# ConverterBoard.net
KiCad netlist of a schematic drawn in EAGLE
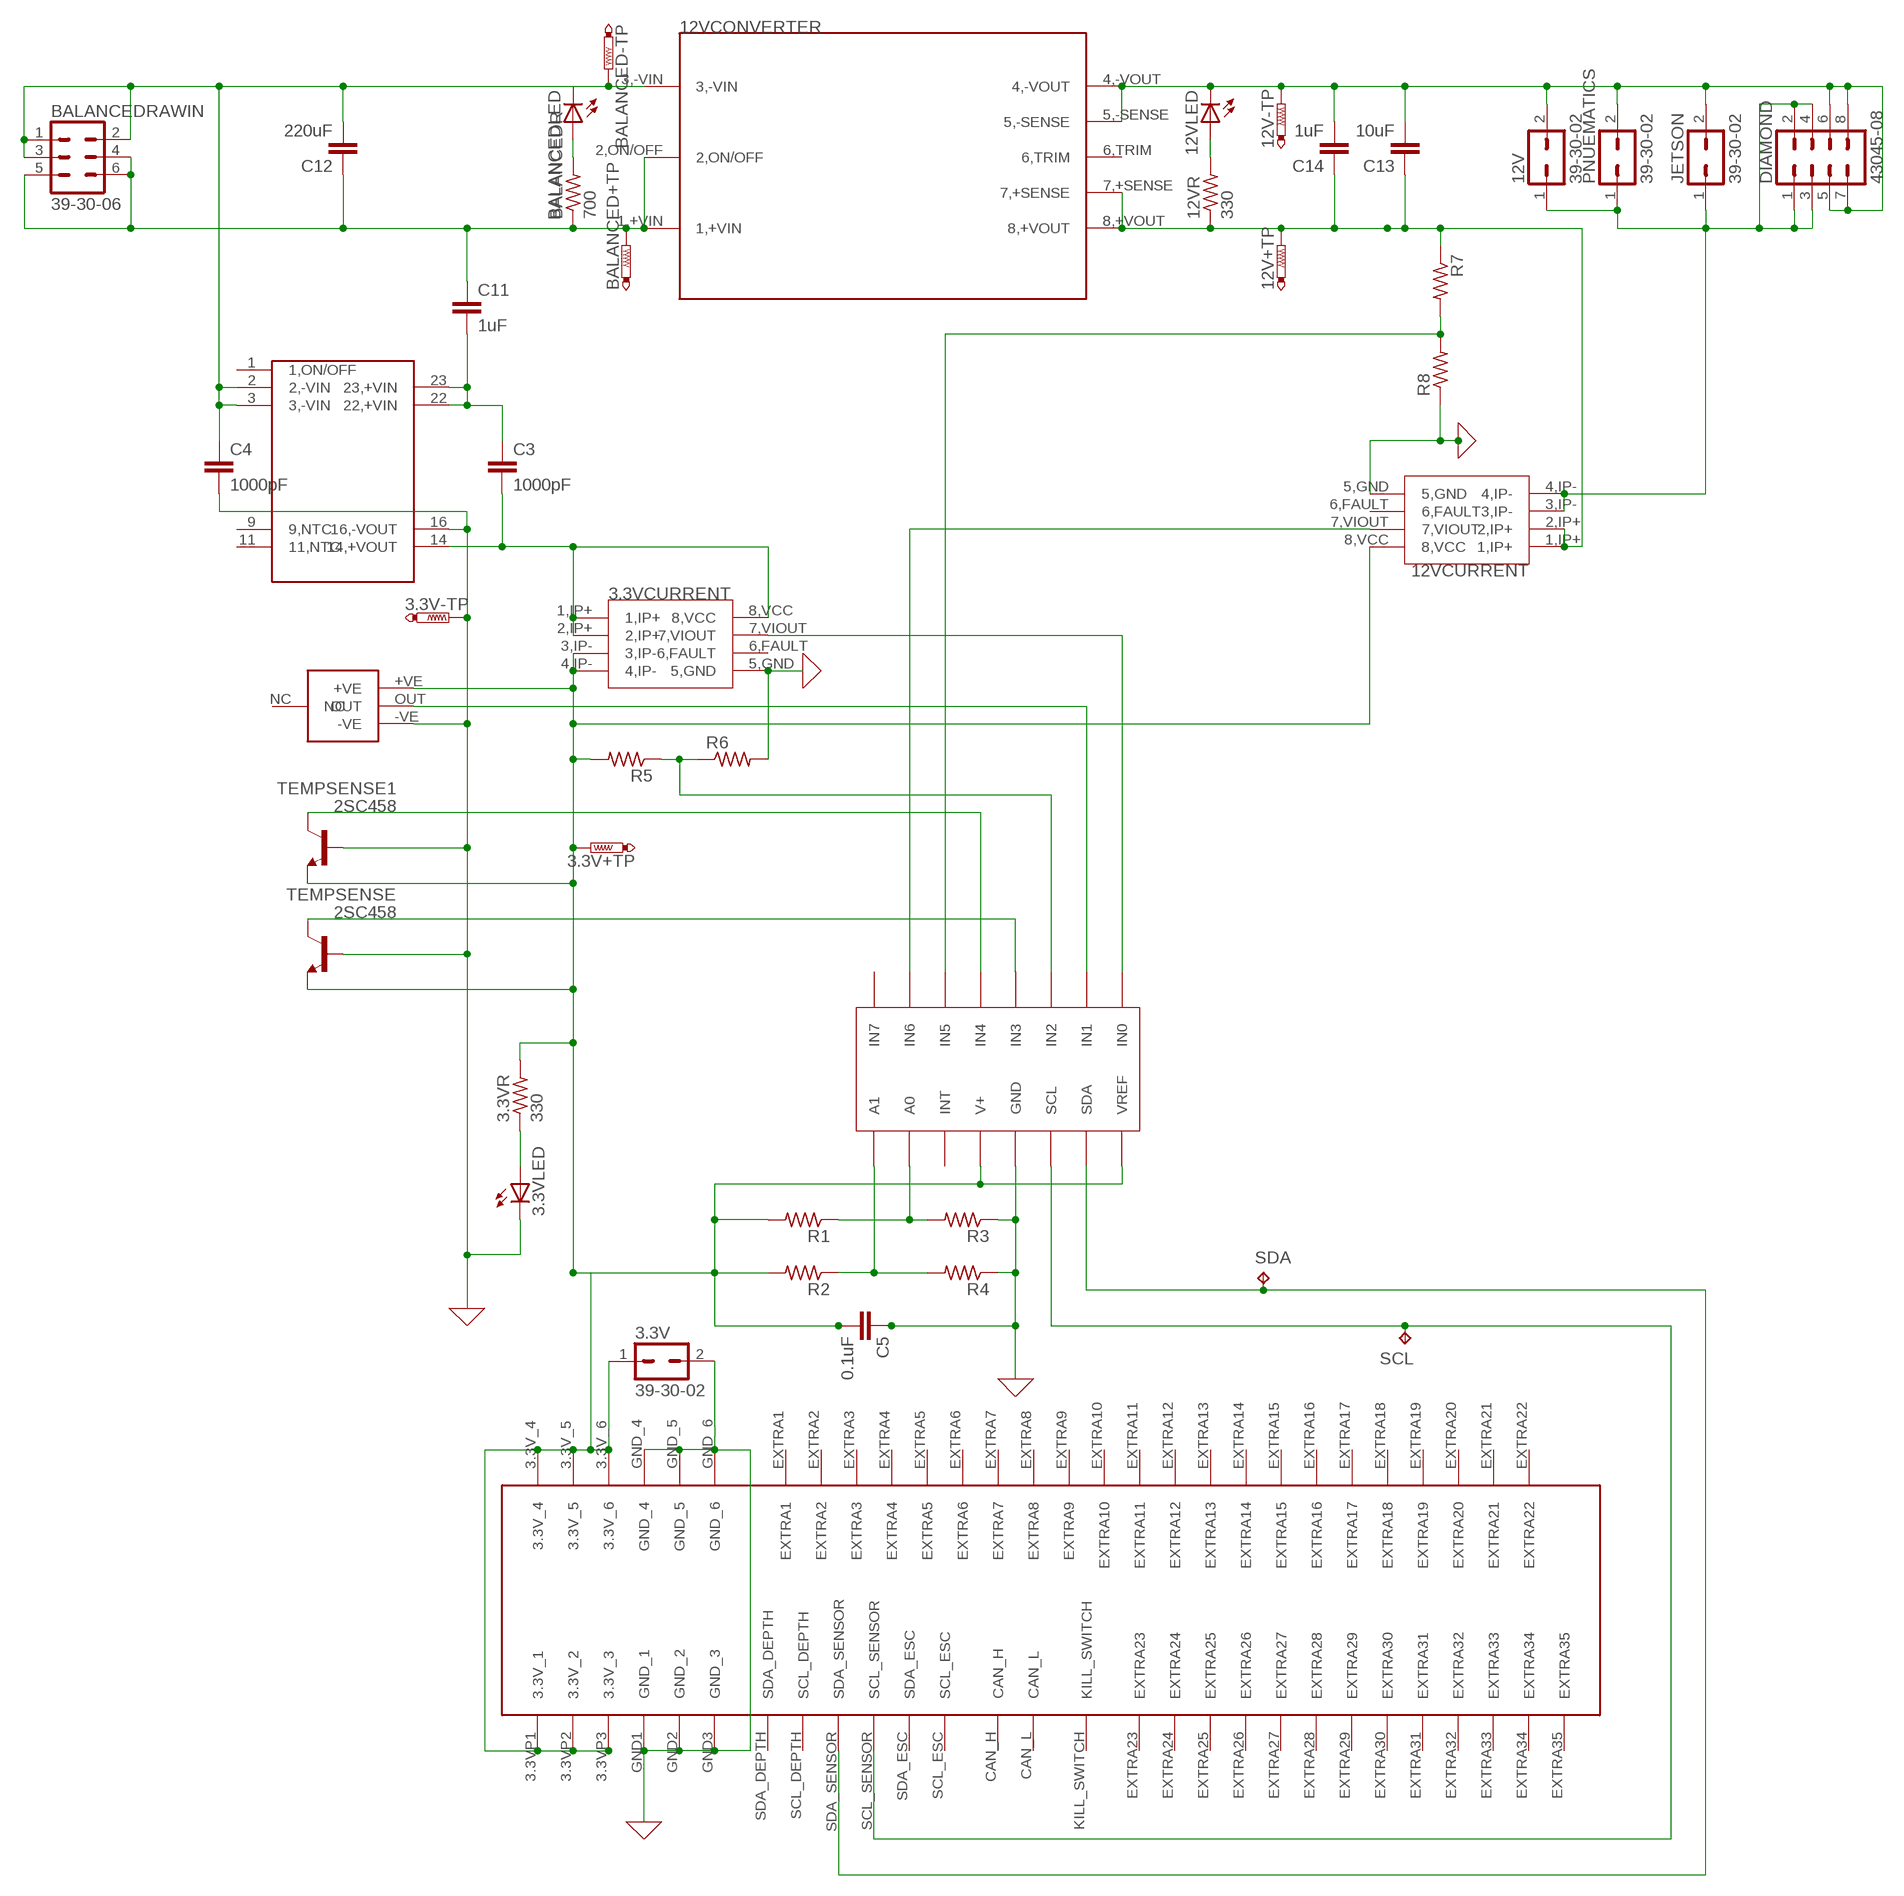
[diagram p0: schematic, sheet 1]

(export (version "E")
  (design (tool "Eeschema 10.0.6"))
  (components
    (comp (ref "3.3V")
      (value "39-30-02")
      (footprint "eagle-import:39-30-_02_")
      (libsource (lib "eagle-import") (part "39-30-?02?"))
    )
    (comp (ref "3.3V+TP")
      (value "PTR1B1,27")
      (footprint "eagle-import:B1,27")
      (libsource (lib "eagle-import") (part "PTR1B1,27"))
    )
    (comp (ref "3.3V-TP")
      (value "PTR1B1,27")
      (footprint "eagle-import:B1,27")
      (libsource (lib "eagle-import") (part "PTR1B1,27"))
    )
    (comp (ref "3.3VCURRENT")
      (value "CURRENTSENS")
      (footprint "eagle-import:CURRENTSENS")
      (libsource (lib "eagle-import") (part "CURRENTSENS"))
    )
    (comp (ref "3.3VLED")
      (value "LTST-S270GKT")
      (footprint "eagle-import:LTST-S270GKT")
      (libsource (lib "eagle-import") (part "LTST-S270GKT"))
    )
    (comp (ref "3.3VR")
      (value "330")
      (footprint "eagle-import:0204_7")
      (libsource (lib "eagle-import") (part "R-US_0204/7"))
    )
    (comp (ref "12V")
      (value "39-30-02")
      (footprint "eagle-import:39-30-_02_")
      (libsource (lib "eagle-import") (part "39-30-?02?"))
    )
    (comp (ref "12V+TP")
      (value "PTR1B1,27")
      (footprint "eagle-import:B1,27")
      (libsource (lib "eagle-import") (part "PTR1B1,27"))
    )
    (comp (ref "12V-TP")
      (value "PTR1B1,27")
      (footprint "eagle-import:B1,27")
      (libsource (lib "eagle-import") (part "PTR1B1,27"))
    )
    (comp (ref "12VCONVERTER")
      (value "12VCONV")
      (footprint "eagle-import:12VCONV")
      (libsource (lib "eagle-import") (part "12VCONV"))
    )
    (comp (ref "12VCURRENT")
      (value "CURRENTSENS")
      (footprint "eagle-import:CURRENTSENS")
      (libsource (lib "eagle-import") (part "CURRENTSENS"))
    )
    (comp (ref "12VLED")
      (value "LTST-S270GKT")
      (footprint "eagle-import:LTST-S270GKT")
      (libsource (lib "eagle-import") (part "LTST-S270GKT"))
    )
    (comp (ref "12VR")
      (value "330")
      (footprint "eagle-import:0204_7")
      (libsource (lib "eagle-import") (part "R-US_0204/7"))
    )
    (comp (ref "ADC")
      (value "ADC128D818")
      (footprint "eagle-import:TSSOP-16")
      (libsource (lib "eagle-import") (part "ADC128D818"))
    )
    (comp (ref "BALANCED+TP")
      (value "PTR1B1,27")
      (footprint "eagle-import:B1,27")
      (libsource (lib "eagle-import") (part "PTR1B1,27"))
    )
    (comp (ref "BALANCED-TP")
      (value "PTR1B1,27")
      (footprint "eagle-import:B1,27")
      (libsource (lib "eagle-import") (part "PTR1B1,27"))
    )
    (comp (ref "BALANCEDLED")
      (value "LTST-S270GKT")
      (footprint "eagle-import:LTST-S270GKT")
      (libsource (lib "eagle-import") (part "LTST-S270GKT"))
    )
    (comp (ref "BALANCEDR")
      (value "700")
      (footprint "eagle-import:0204_7")
      (libsource (lib "eagle-import") (part "R-US_0204/7"))
    )
    (comp (ref "BALANCEDRAWIN")
      (value "39-30-06")
      (footprint "eagle-import:39-30-_06_")
      (libsource (lib "eagle-import") (part "39-30-?06?"))
    )
    (comp (ref "C3")
      (value "1000pF")
      (footprint "eagle-import:C5B3")
      (libsource (lib "eagle-import") (part "C5/3"))
    )
    (comp (ref "C4")
      (value "1000pF")
      (footprint "eagle-import:C5B3")
      (libsource (lib "eagle-import") (part "C5/3"))
    )
    (comp (ref "C5")
      (value "0.1uF")
      (footprint "eagle-import:C2.5-2")
      (libsource (lib "eagle-import") (part "C2.5/2"))
    )
    (comp (ref "C11")
      (value "1uF")
      (footprint "eagle-import:C5B3")
      (libsource (lib "eagle-import") (part "C5/3"))
    )
    (comp (ref "C12")
      (value "220uF")
      (footprint "eagle-import:C5B3")
      (libsource (lib "eagle-import") (part "C5/3"))
    )
    (comp (ref "C13")
      (value "10uF")
      (footprint "eagle-import:C5B3")
      (libsource (lib "eagle-import") (part "C5/3"))
    )
    (comp (ref "C14")
      (value "1uF")
      (footprint "eagle-import:C5B3")
      (libsource (lib "eagle-import") (part "C5/3"))
    )
    (comp (ref "DIAMOND")
      (value "43045-08")
      (footprint "eagle-import:43045-08")
      (libsource (lib "eagle-import") (part "43045-08"))
    )
    (comp (ref "JETSON")
      (value "39-30-02")
      (footprint "eagle-import:39-30-_02_")
      (libsource (lib "eagle-import") (part "39-30-?02?"))
    )
    (comp (ref "PNUEMATICS")
      (value "39-30-02")
      (footprint "eagle-import:39-30-_02_")
      (libsource (lib "eagle-import") (part "39-30-?02?"))
    )
    (comp (ref "R1")
      (value "R-US_0204/7")
      (footprint "eagle-import:0204_7")
      (libsource (lib "eagle-import") (part "R-US_0204/7"))
    )
    (comp (ref "R2")
      (value "R-US_0204/7")
      (footprint "eagle-import:0204_7")
      (libsource (lib "eagle-import") (part "R-US_0204/7"))
    )
    (comp (ref "R3")
      (value "R-US_0204/7")
      (footprint "eagle-import:0204_7")
      (libsource (lib "eagle-import") (part "R-US_0204/7"))
    )
    (comp (ref "R4")
      (value "R-US_0204/7")
      (footprint "eagle-import:0204_7")
      (libsource (lib "eagle-import") (part "R-US_0204/7"))
    )
    (comp (ref "R5")
      (value "R-US_0204/7")
      (footprint "eagle-import:0204_7")
      (libsource (lib "eagle-import") (part "R-US_0204/7"))
    )
    (comp (ref "R6")
      (value "R-US_0204/7")
      (footprint "eagle-import:0204_7")
      (libsource (lib "eagle-import") (part "R-US_0204/7"))
    )
    (comp (ref "R7")
      (value "R-US_0204/7")
      (footprint "eagle-import:0204_7")
      (libsource (lib "eagle-import") (part "R-US_0204/7"))
    )
    (comp (ref "R8")
      (value "R-US_0204/7")
      (footprint "eagle-import:0204_7")
      (libsource (lib "eagle-import") (part "R-US_0204/7"))
    )
    (comp (ref "SCL")
      (value "TPPAD1-20")
      (footprint "eagle-import:P1-20")
      (libsource (lib "eagle-import") (part "TPPAD1-20"))
    )
    (comp (ref "SDA")
      (value "TPPAD1-20")
      (footprint "eagle-import:P1-20")
      (libsource (lib "eagle-import") (part "TPPAD1-20"))
    )
    (comp (ref "TEMPSENSE")
      (value "2SC458")
      (footprint "eagle-import:TO92-ECB")
      (libsource (lib "eagle-import") (part "2SC458"))
    )
    (comp (ref "TEMPSENSE1")
      (value "2SC458")
      (footprint "eagle-import:TO92-ECB")
      (libsource (lib "eagle-import") (part "2SC458"))
    )
    (comp (ref "U$2")
      (value "3.3VCONV")
      (footprint "eagle-import:3.3VCONV")
      (libsource (lib "eagle-import") (part "3.3VCONV"))
    )
    (comp (ref "U$3")
      (value "5530843")
      (footprint "eagle-import:5530843-6-BOARDFINGERS")
      (libsource (lib "eagle-import") (part "5530843"))
    )
    (comp (ref "U$6")
      (value "HUMIDITYSENSOR")
      (footprint "eagle-import:HUMIDITYSENSOR")
      (libsource (lib "eagle-import") (part "HUMIDITYSENSOR"))
    )
  )
  (nets
    (net (code "1") (name "GND") (class "Default")
      (node (ref "12V") (pin "2") (pinfunction "2_2") (pintype "passive"))
      (node (ref "12V-TP") (pin "TP") (pinfunction "TP_TP") (pintype "input"))
      (node (ref "12VCONVERTER") (pin "4,-VOUT") (pinfunction "4,-VOUT_4,-VOUT") (pintype "bidirectional"))
      (node (ref "12VCONVERTER") (pin "5,-SENSE") (pinfunction "5,-SENSE_5,-SENSE") (pintype "bidirectional"))
      (node (ref "12VCURRENT") (pin "5,GND") (pinfunction "5,GND_5,GND") (pintype "bidirectional"))
      (node (ref "12VLED") (pin "CATHODE") (pinfunction "C_CATHODE") (pintype "passive"))
      (node (ref "3.3V") (pin "2") (pinfunction "2_2") (pintype "passive"))
      (node (ref "3.3V-TP") (pin "TP") (pinfunction "TP_TP") (pintype "input"))
      (node (ref "3.3VCURRENT") (pin "5,GND") (pinfunction "5,GND_5,GND") (pintype "bidirectional"))
      (node (ref "3.3VLED") (pin "CATHODE") (pinfunction "C_CATHODE") (pintype "passive"))
      (node (ref "ADC") (pin "GND") (pinfunction "GND_GND") (pintype "bidirectional"))
      (node (ref "C13") (pin "2") (pinfunction "2_2") (pintype "passive"))
      (node (ref "C14") (pin "2") (pinfunction "2_2") (pintype "passive"))
      (node (ref "C4") (pin "2") (pinfunction "2_2") (pintype "passive"))
      (node (ref "C5") (pin "1") (pinfunction "1_1") (pintype "passive"))
      (node (ref "DIAMOND") (pin "5") (pinfunction "5_5") (pintype "passive"))
      (node (ref "DIAMOND") (pin "6") (pinfunction "6_6") (pintype "passive"))
      (node (ref "DIAMOND") (pin "7") (pinfunction "7_7") (pintype "passive"))
      (node (ref "DIAMOND") (pin "8") (pinfunction "8_8") (pintype "passive"))
      (node (ref "JETSON") (pin "2") (pinfunction "2_2") (pintype "passive"))
      (node (ref "PNUEMATICS") (pin "2") (pinfunction "2_2") (pintype "passive"))
      (node (ref "R3") (pin "1") (pinfunction "1_1") (pintype "passive"))
      (node (ref "R4") (pin "1") (pinfunction "1_1") (pintype "passive"))
      (node (ref "R6") (pin "2") (pinfunction "2_2") (pintype "passive"))
      (node (ref "R8") (pin "1") (pinfunction "1_1") (pintype "passive"))
      (node (ref "TEMPSENSE") (pin "B") (pinfunction "B_B") (pintype "passive"))
      (node (ref "TEMPSENSE1") (pin "B") (pinfunction "B_B") (pintype "passive"))
      (node (ref "U$2") (pin "16") (pinfunction "16,-VOUT_16") (pintype "bidirectional"))
      (node (ref "U$3") (pin "GND1") (pinfunction "GND_1_GND1") (pintype "bidirectional"))
      (node (ref "U$3") (pin "GND2") (pinfunction "GND_2_GND2") (pintype "bidirectional"))
      (node (ref "U$3") (pin "GND3") (pinfunction "GND_3_GND3") (pintype "bidirectional"))
      (node (ref "U$3") (pin "GND_4") (pinfunction "GND_4_GND_4") (pintype "bidirectional"))
      (node (ref "U$3") (pin "GND_5") (pinfunction "GND_5_GND_5") (pintype "bidirectional"))
      (node (ref "U$3") (pin "GND_6") (pinfunction "GND_6_GND_6") (pintype "bidirectional"))
      (node (ref "U$6") (pin "-VE") (pinfunction "-VE_-VE") (pintype "bidirectional"))
    )
    (net (code "2") (name "Net-(3.3VCURRENT-Pad7,VIOUT)") (class "Default")
      (node (ref "3.3VCURRENT") (pin "7,VIOUT") (pinfunction "7,VIOUT_7,VIOUT") (pintype "bidirectional"))
      (node (ref "ADC") (pin "IN0") (pinfunction "IN0_IN0") (pintype "bidirectional"))
    )
    (net (code "3") (name "Net-(3.3VLED-A)") (class "Default")
      (node (ref "3.3VLED") (pin "ANODE") (pinfunction "A_ANODE") (pintype "passive"))
      (node (ref "3.3VR") (pin "1") (pinfunction "1_1") (pintype "passive"))
    )
    (net (code "4") (name "Net-(12V+TP-PadTP)") (class "Default")
      (node (ref "12V+TP") (pin "TP") (pinfunction "TP_TP") (pintype "input"))
      (node (ref "12VCONVERTER") (pin "7,+SENSE") (pinfunction "7,+SENSE_7,+SENSE") (pintype "bidirectional"))
      (node (ref "12VCONVERTER") (pin "8,+VOUT") (pinfunction "8,+VOUT_8,+VOUT") (pintype "bidirectional"))
      (node (ref "12VCURRENT") (pin "1,IP+") (pinfunction "1,IP+_1,IP+") (pintype "bidirectional"))
      (node (ref "12VCURRENT") (pin "2,IP+") (pinfunction "2,IP+_2,IP+") (pintype "bidirectional"))
      (node (ref "12VR") (pin "1") (pinfunction "1_1") (pintype "passive"))
      (node (ref "C13") (pin "1") (pinfunction "1_1") (pintype "passive"))
      (node (ref "C14") (pin "1") (pinfunction "1_1") (pintype "passive"))
      (node (ref "R7") (pin "1") (pinfunction "1_1") (pintype "passive"))
    )
    (net (code "5") (name "Net-(12V-Pad1)") (class "Default")
      (node (ref "12V") (pin "1") (pinfunction "1_1") (pintype "passive"))
      (node (ref "12VCURRENT") (pin "3,IP-") (pinfunction "3,IP-_3,IP-") (pintype "bidirectional"))
      (node (ref "12VCURRENT") (pin "4,IP-") (pinfunction "4,IP-_4,IP-") (pintype "bidirectional"))
      (node (ref "DIAMOND") (pin "1") (pinfunction "1_1") (pintype "passive"))
      (node (ref "DIAMOND") (pin "2") (pinfunction "2_2") (pintype "passive"))
      (node (ref "DIAMOND") (pin "3") (pinfunction "3_3") (pintype "passive"))
      (node (ref "DIAMOND") (pin "4") (pinfunction "4_4") (pintype "passive"))
      (node (ref "JETSON") (pin "1") (pinfunction "1_1") (pintype "passive"))
      (node (ref "PNUEMATICS") (pin "1") (pinfunction "1_1") (pintype "passive"))
    )
    (net (code "6") (name "Net-(12VCONVERTER-Pad1,+VIN)") (class "Default")
      (node (ref "12VCONVERTER") (pin "1,+VIN") (pinfunction "1,+VIN_1,+VIN") (pintype "bidirectional"))
      (node (ref "12VCONVERTER") (pin "2,ON/OFF") (pinfunction "2,ON/OFF_2,ON/OFF") (pintype "bidirectional"))
      (node (ref "BALANCED+TP") (pin "TP") (pinfunction "TP_TP") (pintype "input"))
      (node (ref "BALANCEDR") (pin "1") (pinfunction "1_1") (pintype "passive"))
      (node (ref "BALANCEDRAWIN") (pin "4") (pinfunction "4_4") (pintype "passive"))
      (node (ref "BALANCEDRAWIN") (pin "5") (pinfunction "5_5") (pintype "passive"))
      (node (ref "BALANCEDRAWIN") (pin "6") (pinfunction "6_6") (pintype "passive"))
      (node (ref "C11") (pin "1") (pinfunction "1_1") (pintype "passive"))
      (node (ref "C12") (pin "1") (pinfunction "1_1") (pintype "passive"))
    )
    (net (code "7") (name "Net-(12VCURRENT-Pad7,VIOUT)") (class "Default")
      (node (ref "12VCURRENT") (pin "7,VIOUT") (pinfunction "7,VIOUT_7,VIOUT") (pintype "bidirectional"))
      (node (ref "ADC") (pin "IN6") (pinfunction "IN6_IN6") (pintype "bidirectional"))
    )
    (net (code "8") (name "Net-(12VLED-A)") (class "Default")
      (node (ref "12VLED") (pin "ANODE") (pinfunction "A_ANODE") (pintype "passive"))
      (node (ref "12VR") (pin "2") (pinfunction "2_2") (pintype "passive"))
    )
    (net (code "9") (name "Net-(ADC-PadA0)") (class "Default")
      (node (ref "ADC") (pin "A0") (pinfunction "A0_A0") (pintype "bidirectional"))
      (node (ref "R1") (pin "1") (pinfunction "1_1") (pintype "passive"))
      (node (ref "R3") (pin "2") (pinfunction "2_2") (pintype "passive"))
    )
    (net (code "10") (name "Net-(ADC-PadA1)") (class "Default")
      (node (ref "ADC") (pin "A1") (pinfunction "A1_A1") (pintype "bidirectional"))
      (node (ref "R2") (pin "1") (pinfunction "1_1") (pintype "passive"))
      (node (ref "R4") (pin "2") (pinfunction "2_2") (pintype "passive"))
    )
    (net (code "11") (name "Net-(ADC-PadIN1)") (class "Default")
      (node (ref "ADC") (pin "IN1") (pinfunction "IN1_IN1") (pintype "bidirectional"))
      (node (ref "U$6") (pin "OUT") (pinfunction "OUT_OUT") (pintype "bidirectional"))
    )
    (net (code "12") (name "Net-(ADC-PadIN2)") (class "Default")
      (node (ref "ADC") (pin "IN2") (pinfunction "IN2_IN2") (pintype "bidirectional"))
      (node (ref "R5") (pin "1") (pinfunction "1_1") (pintype "passive"))
      (node (ref "R6") (pin "1") (pinfunction "1_1") (pintype "passive"))
    )
    (net (code "13") (name "Net-(ADC-PadIN3)") (class "Default")
      (node (ref "ADC") (pin "IN3") (pinfunction "IN3_IN3") (pintype "bidirectional"))
      (node (ref "TEMPSENSE") (pin "C") (pinfunction "C_C") (pintype "passive"))
    )
    (net (code "14") (name "Net-(ADC-PadIN4)") (class "Default")
      (node (ref "ADC") (pin "IN4") (pinfunction "IN4_IN4") (pintype "bidirectional"))
      (node (ref "TEMPSENSE1") (pin "C") (pinfunction "C_C") (pintype "passive"))
    )
    (net (code "15") (name "Net-(ADC-PadIN5)") (class "Default")
      (node (ref "ADC") (pin "IN5") (pinfunction "IN5_IN5") (pintype "bidirectional"))
      (node (ref "R7") (pin "2") (pinfunction "2_2") (pintype "passive"))
      (node (ref "R8") (pin "2") (pinfunction "2_2") (pintype "passive"))
    )
    (net (code "16") (name "Net-(ADC-PadSCL)") (class "Default")
      (node (ref "ADC") (pin "SCL") (pinfunction "SCL_SCL") (pintype "bidirectional"))
      (node (ref "SCL") (pin "TP") (pinfunction "TP_TP") (pintype "input"))
      (node (ref "U$3") (pin "SCL_SENSOR") (pinfunction "SCL_SENSOR_SCL_SENSOR") (pintype "bidirectional"))
    )
    (net (code "17") (name "Net-(ADC-PadSDA)") (class "Default")
      (node (ref "ADC") (pin "SDA") (pinfunction "SDA_SDA") (pintype "bidirectional"))
      (node (ref "SDA") (pin "TP") (pinfunction "TP_TP") (pintype "input"))
      (node (ref "U$3") (pin "SDA_SENSOR") (pinfunction "SDA_SENSOR_SDA_SENSOR") (pintype "bidirectional"))
    )
    (net (code "18") (name "Net-(BALANCEDLED-A)") (class "Default")
      (node (ref "BALANCEDLED") (pin "ANODE") (pinfunction "A_ANODE") (pintype "passive"))
      (node (ref "BALANCEDR") (pin "2") (pinfunction "2_2") (pintype "passive"))
    )
    (net (code "19") (name "Net-(BALANCEDLED-C)") (class "Default")
      (node (ref "12VCONVERTER") (pin "3,-VIN") (pinfunction "3,-VIN_3,-VIN") (pintype "bidirectional"))
      (node (ref "BALANCED-TP") (pin "TP") (pinfunction "TP_TP") (pintype "input"))
      (node (ref "BALANCEDLED") (pin "CATHODE") (pinfunction "C_CATHODE") (pintype "passive"))
      (node (ref "BALANCEDRAWIN") (pin "1") (pinfunction "1_1") (pintype "passive"))
      (node (ref "BALANCEDRAWIN") (pin "2") (pinfunction "2_2") (pintype "passive"))
      (node (ref "BALANCEDRAWIN") (pin "3") (pinfunction "3_3") (pintype "passive"))
      (node (ref "C12") (pin "2") (pinfunction "2_2") (pintype "passive"))
      (node (ref "C4") (pin "1") (pinfunction "1_1") (pintype "passive"))
      (node (ref "U$2") (pin "2") (pinfunction "2,-VIN_2") (pintype "bidirectional"))
      (node (ref "U$2") (pin "3") (pinfunction "3,-VIN_3") (pintype "bidirectional"))
    )
    (net (code "20") (name "Net-(U$2-14,+VOUT)") (class "Default")
      (node (ref "3.3VCURRENT") (pin "1,IP+") (pinfunction "1,IP+_1,IP+") (pintype "bidirectional"))
      (node (ref "3.3VCURRENT") (pin "2,IP+") (pinfunction "2,IP+_2,IP+") (pintype "bidirectional"))
      (node (ref "3.3VCURRENT") (pin "8,VCC") (pinfunction "8,VCC_8,VCC") (pintype "bidirectional"))
      (node (ref "C3") (pin "2") (pinfunction "2_2") (pintype "passive"))
      (node (ref "U$2") (pin "14") (pinfunction "14,+VOUT_14") (pintype "bidirectional"))
    )
    (net (code "21") (name "Net-(U$2-22,+VIN)") (class "Default")
      (node (ref "C11") (pin "2") (pinfunction "2_2") (pintype "passive"))
      (node (ref "C3") (pin "1") (pinfunction "1_1") (pintype "passive"))
      (node (ref "U$2") (pin "22") (pinfunction "22,+VIN_22") (pintype "bidirectional"))
      (node (ref "U$2") (pin "23") (pinfunction "23,+VIN_23") (pintype "bidirectional"))
    )
    (net (code "22") (name "Net-(U$3-3.3V_1)") (class "Default")
      (node (ref "12VCURRENT") (pin "8,VCC") (pinfunction "8,VCC_8,VCC") (pintype "bidirectional"))
      (node (ref "3.3V") (pin "1") (pinfunction "1_1") (pintype "passive"))
      (node (ref "3.3V+TP") (pin "TP") (pinfunction "TP_TP") (pintype "input"))
      (node (ref "3.3VCURRENT") (pin "3,IP-") (pinfunction "3,IP-_3,IP-") (pintype "bidirectional"))
      (node (ref "3.3VCURRENT") (pin "4,IP-") (pinfunction "4,IP-_4,IP-") (pintype "bidirectional"))
      (node (ref "3.3VR") (pin "2") (pinfunction "2_2") (pintype "passive"))
      (node (ref "ADC") (pin "V+") (pinfunction "V+_V+") (pintype "bidirectional"))
      (node (ref "ADC") (pin "VREF") (pinfunction "VREF_VREF") (pintype "bidirectional"))
      (node (ref "C5") (pin "2") (pinfunction "2_2") (pintype "passive"))
      (node (ref "R1") (pin "2") (pinfunction "2_2") (pintype "passive"))
      (node (ref "R2") (pin "2") (pinfunction "2_2") (pintype "passive"))
      (node (ref "R5") (pin "2") (pinfunction "2_2") (pintype "passive"))
      (node (ref "TEMPSENSE") (pin "E") (pinfunction "E_E") (pintype "passive"))
      (node (ref "TEMPSENSE1") (pin "E") (pinfunction "E_E") (pintype "passive"))
      (node (ref "U$3") (pin "3.3VP1") (pinfunction "3.3V_1_3.3VP1") (pintype "bidirectional"))
      (node (ref "U$3") (pin "3.3VP2") (pinfunction "3.3V_2_3.3VP2") (pintype "bidirectional"))
      (node (ref "U$3") (pin "3.3VP3") (pinfunction "3.3V_3_3.3VP3") (pintype "bidirectional"))
      (node (ref "U$3") (pin "3.3V_4") (pinfunction "3.3V_4_3.3V_4") (pintype "bidirectional"))
      (node (ref "U$3") (pin "3.3V_5") (pinfunction "3.3V_5_3.3V_5") (pintype "bidirectional"))
      (node (ref "U$3") (pin "3.3V_6") (pinfunction "3.3V_6_3.3V_6") (pintype "bidirectional"))
      (node (ref "U$6") (pin "+VE") (pinfunction "+VE_+VE") (pintype "bidirectional"))
    )
    (net (code "23") (name "unconnected-(3.3VCURRENT-Pad6,FAULT)") (class "Default")
      (node (ref "3.3VCURRENT") (pin "6,FAULT") (pinfunction "6,FAULT_6,FAULT") (pintype "bidirectional"))
    )
    (net (code "24") (name "unconnected-(12VCONVERTER-Pad6,TRIM)") (class "Default")
      (node (ref "12VCONVERTER") (pin "6,TRIM") (pinfunction "6,TRIM_6,TRIM") (pintype "bidirectional"))
    )
    (net (code "25") (name "unconnected-(12VCURRENT-Pad6,FAULT)") (class "Default")
      (node (ref "12VCURRENT") (pin "6,FAULT") (pinfunction "6,FAULT_6,FAULT") (pintype "bidirectional"))
    )
    (net (code "26") (name "unconnected-(ADC-PadIN7)") (class "Default")
      (node (ref "ADC") (pin "IN7") (pinfunction "IN7_IN7") (pintype "bidirectional"))
    )
    (net (code "27") (name "unconnected-(ADC-PadINT)") (class "Default")
      (node (ref "ADC") (pin "INT") (pinfunction "INT_INT") (pintype "bidirectional"))
    )
    (net (code "28") (name "unconnected-(U$2-1,ON{slash}OFF-Pad1)") (class "Default")
      (node (ref "U$2") (pin "1") (pinfunction "1,ON/OFF_1") (pintype "bidirectional"))
    )
    (net (code "29") (name "unconnected-(U$2-9,NTC-Pad9)") (class "Default")
      (node (ref "U$2") (pin "9") (pinfunction "9,NTC_9") (pintype "bidirectional"))
    )
    (net (code "30") (name "unconnected-(U$2-11,NTC-Pad11)") (class "Default")
      (node (ref "U$2") (pin "11") (pinfunction "11,NTC_11") (pintype "bidirectional"))
    )
    (net (code "31") (name "unconnected-(U$3-PadCAN_H)") (class "Default")
      (node (ref "U$3") (pin "CAN_H") (pinfunction "CAN_H_CAN_H") (pintype "bidirectional"))
    )
    (net (code "32") (name "unconnected-(U$3-PadCAN_L)") (class "Default")
      (node (ref "U$3") (pin "CAN_L") (pinfunction "CAN_L_CAN_L") (pintype "bidirectional"))
    )
    (net (code "33") (name "unconnected-(U$3-PadEXTRA1)") (class "Default")
      (node (ref "U$3") (pin "EXTRA1") (pinfunction "EXTRA1_EXTRA1") (pintype "bidirectional"))
    )
    (net (code "34") (name "unconnected-(U$3-PadEXTRA2)") (class "Default")
      (node (ref "U$3") (pin "EXTRA2") (pinfunction "EXTRA2_EXTRA2") (pintype "bidirectional"))
    )
    (net (code "35") (name "unconnected-(U$3-PadEXTRA3)") (class "Default")
      (node (ref "U$3") (pin "EXTRA3") (pinfunction "EXTRA3_EXTRA3") (pintype "bidirectional"))
    )
    (net (code "36") (name "unconnected-(U$3-PadEXTRA4)") (class "Default")
      (node (ref "U$3") (pin "EXTRA4") (pinfunction "EXTRA4_EXTRA4") (pintype "bidirectional"))
    )
    (net (code "37") (name "unconnected-(U$3-PadEXTRA5)") (class "Default")
      (node (ref "U$3") (pin "EXTRA5") (pinfunction "EXTRA5_EXTRA5") (pintype "bidirectional"))
    )
    (net (code "38") (name "unconnected-(U$3-PadEXTRA6)") (class "Default")
      (node (ref "U$3") (pin "EXTRA6") (pinfunction "EXTRA6_EXTRA6") (pintype "bidirectional"))
    )
    (net (code "39") (name "unconnected-(U$3-PadEXTRA7)") (class "Default")
      (node (ref "U$3") (pin "EXTRA7") (pinfunction "EXTRA7_EXTRA7") (pintype "bidirectional"))
    )
    (net (code "40") (name "unconnected-(U$3-PadEXTRA8)") (class "Default")
      (node (ref "U$3") (pin "EXTRA8") (pinfunction "EXTRA8_EXTRA8") (pintype "bidirectional"))
    )
    (net (code "41") (name "unconnected-(U$3-PadEXTRA9)") (class "Default")
      (node (ref "U$3") (pin "EXTRA9") (pinfunction "EXTRA9_EXTRA9") (pintype "bidirectional"))
    )
    (net (code "42") (name "unconnected-(U$3-PadEXTRA10)") (class "Default")
      (node (ref "U$3") (pin "EXTRA10") (pinfunction "EXTRA10_EXTRA10") (pintype "bidirectional"))
    )
    (net (code "43") (name "unconnected-(U$3-PadEXTRA11)") (class "Default")
      (node (ref "U$3") (pin "EXTRA11") (pinfunction "EXTRA11_EXTRA11") (pintype "bidirectional"))
    )
    (net (code "44") (name "unconnected-(U$3-PadEXTRA12)") (class "Default")
      (node (ref "U$3") (pin "EXTRA12") (pinfunction "EXTRA12_EXTRA12") (pintype "bidirectional"))
    )
    (net (code "45") (name "unconnected-(U$3-PadEXTRA13)") (class "Default")
      (node (ref "U$3") (pin "EXTRA13") (pinfunction "EXTRA13_EXTRA13") (pintype "bidirectional"))
    )
    (net (code "46") (name "unconnected-(U$3-PadEXTRA14)") (class "Default")
      (node (ref "U$3") (pin "EXTRA14") (pinfunction "EXTRA14_EXTRA14") (pintype "bidirectional"))
    )
    (net (code "47") (name "unconnected-(U$3-PadEXTRA15)") (class "Default")
      (node (ref "U$3") (pin "EXTRA15") (pinfunction "EXTRA15_EXTRA15") (pintype "bidirectional"))
    )
    (net (code "48") (name "unconnected-(U$3-PadEXTRA16)") (class "Default")
      (node (ref "U$3") (pin "EXTRA16") (pinfunction "EXTRA16_EXTRA16") (pintype "bidirectional"))
    )
    (net (code "49") (name "unconnected-(U$3-PadEXTRA17)") (class "Default")
      (node (ref "U$3") (pin "EXTRA17") (pinfunction "EXTRA17_EXTRA17") (pintype "bidirectional"))
    )
    (net (code "50") (name "unconnected-(U$3-PadEXTRA18)") (class "Default")
      (node (ref "U$3") (pin "EXTRA18") (pinfunction "EXTRA18_EXTRA18") (pintype "bidirectional"))
    )
    (net (code "51") (name "unconnected-(U$3-PadEXTRA19)") (class "Default")
      (node (ref "U$3") (pin "EXTRA19") (pinfunction "EXTRA19_EXTRA19") (pintype "bidirectional"))
    )
    (net (code "52") (name "unconnected-(U$3-PadEXTRA20)") (class "Default")
      (node (ref "U$3") (pin "EXTRA20") (pinfunction "EXTRA20_EXTRA20") (pintype "bidirectional"))
    )
    (net (code "53") (name "unconnected-(U$3-PadEXTRA21)") (class "Default")
      (node (ref "U$3") (pin "EXTRA21") (pinfunction "EXTRA21_EXTRA21") (pintype "bidirectional"))
    )
    (net (code "54") (name "unconnected-(U$3-PadEXTRA22)") (class "Default")
      (node (ref "U$3") (pin "EXTRA22") (pinfunction "EXTRA22_EXTRA22") (pintype "bidirectional"))
    )
    (net (code "55") (name "unconnected-(U$3-PadEXTRA23)") (class "Default")
      (node (ref "U$3") (pin "EXTRA23") (pinfunction "EXTRA23_EXTRA23") (pintype "bidirectional"))
    )
    (net (code "56") (name "unconnected-(U$3-PadEXTRA24)") (class "Default")
      (node (ref "U$3") (pin "EXTRA24") (pinfunction "EXTRA24_EXTRA24") (pintype "bidirectional"))
    )
    (net (code "57") (name "unconnected-(U$3-PadEXTRA25)") (class "Default")
      (node (ref "U$3") (pin "EXTRA25") (pinfunction "EXTRA25_EXTRA25") (pintype "bidirectional"))
    )
    (net (code "58") (name "unconnected-(U$3-PadEXTRA26)") (class "Default")
      (node (ref "U$3") (pin "EXTRA26") (pinfunction "EXTRA26_EXTRA26") (pintype "bidirectional"))
    )
    (net (code "59") (name "unconnected-(U$3-PadEXTRA27)") (class "Default")
      (node (ref "U$3") (pin "EXTRA27") (pinfunction "EXTRA27_EXTRA27") (pintype "bidirectional"))
    )
    (net (code "60") (name "unconnected-(U$3-PadEXTRA28)") (class "Default")
      (node (ref "U$3") (pin "EXTRA28") (pinfunction "EXTRA28_EXTRA28") (pintype "bidirectional"))
    )
    (net (code "61") (name "unconnected-(U$3-PadEXTRA29)") (class "Default")
      (node (ref "U$3") (pin "EXTRA29") (pinfunction "EXTRA29_EXTRA29") (pintype "bidirectional"))
    )
    (net (code "62") (name "unconnected-(U$3-PadEXTRA30)") (class "Default")
      (node (ref "U$3") (pin "EXTRA30") (pinfunction "EXTRA30_EXTRA30") (pintype "bidirectional"))
    )
    (net (code "63") (name "unconnected-(U$3-PadEXTRA31)") (class "Default")
      (node (ref "U$3") (pin "EXTRA31") (pinfunction "EXTRA31_EXTRA31") (pintype "bidirectional"))
    )
    (net (code "64") (name "unconnected-(U$3-PadEXTRA32)") (class "Default")
      (node (ref "U$3") (pin "EXTRA32") (pinfunction "EXTRA32_EXTRA32") (pintype "bidirectional"))
    )
    (net (code "65") (name "unconnected-(U$3-PadEXTRA33)") (class "Default")
      (node (ref "U$3") (pin "EXTRA33") (pinfunction "EXTRA33_EXTRA33") (pintype "bidirectional"))
    )
    (net (code "66") (name "unconnected-(U$3-PadEXTRA34)") (class "Default")
      (node (ref "U$3") (pin "EXTRA34") (pinfunction "EXTRA34_EXTRA34") (pintype "bidirectional"))
    )
    (net (code "67") (name "unconnected-(U$3-PadEXTRA35)") (class "Default")
      (node (ref "U$3") (pin "EXTRA35") (pinfunction "EXTRA35_EXTRA35") (pintype "bidirectional"))
    )
    (net (code "68") (name "unconnected-(U$3-PadKILL_SWITCH)") (class "Default")
      (node (ref "U$3") (pin "KILL_SWITCH") (pinfunction "KILL_SWITCH_KILL_SWITCH") (pintype "bidirectional"))
    )
    (net (code "69") (name "unconnected-(U$3-PadSCL_DEPTH)") (class "Default")
      (node (ref "U$3") (pin "SCL_DEPTH") (pinfunction "SCL_DEPTH_SCL_DEPTH") (pintype "bidirectional"))
    )
    (net (code "70") (name "unconnected-(U$3-PadSCL_ESC)") (class "Default")
      (node (ref "U$3") (pin "SCL_ESC") (pinfunction "SCL_ESC_SCL_ESC") (pintype "bidirectional"))
    )
    (net (code "71") (name "unconnected-(U$3-PadSDA_DEPTH)") (class "Default")
      (node (ref "U$3") (pin "SDA_DEPTH") (pinfunction "SDA_DEPTH_SDA_DEPTH") (pintype "bidirectional"))
    )
    (net (code "72") (name "unconnected-(U$3-PadSDA_ESC)") (class "Default")
      (node (ref "U$3") (pin "SDA_ESC") (pinfunction "SDA_ESC_SDA_ESC") (pintype "bidirectional"))
    )
    (net (code "73") (name "unconnected-(U$6-PadNC)") (class "Default")
      (node (ref "U$6") (pin "NC") (pinfunction "NC_NC") (pintype "bidirectional"))
    )
  )
)
